# piezo-buffer-and-preamp-ritter_V0-1-thru.net
KiCad netlist of a schematic drawn in EAGLE
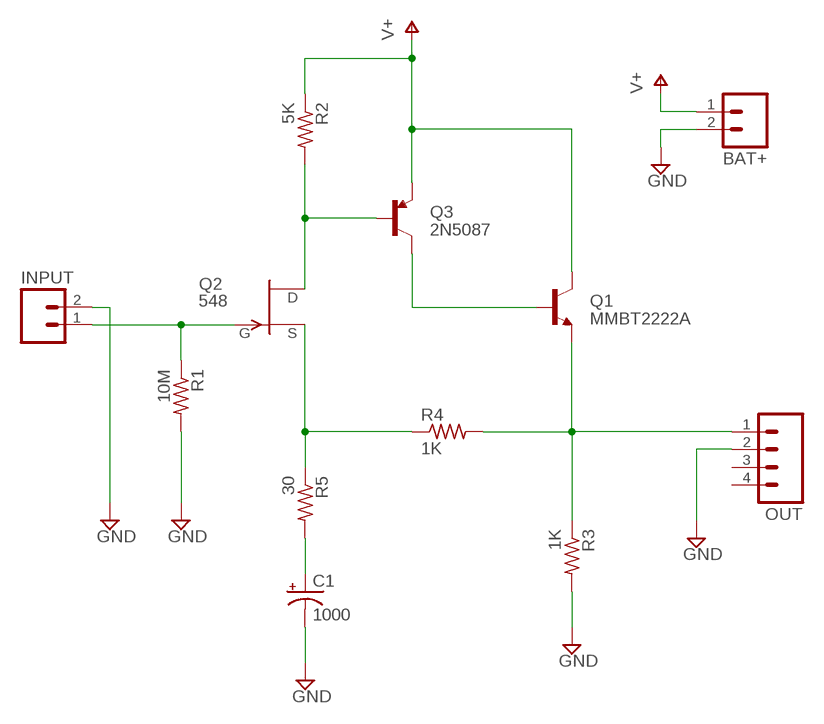
[diagram p0: schematic, sheet 1]

(export (version "E")
  (design (tool "Eeschema 10.0.6"))
  (components
    (comp (ref "BAT+")
      (value "M02LOCK")
      (footprint "eagle-import:1X02_LOCK")
      (libsource (lib "eagle-import") (part "M02LOCK"))
    )
    (comp (ref "C1")
      (value "1000")
      (footprint "eagle-import:CPOL-RADIAL-10UF-25V")
      (libsource (lib "eagle-import") (part "CAP_POLPTH2"))
    )
    (comp (ref "INPUT")
      (value "M02LOCK")
      (footprint "eagle-import:1X02_LOCK")
      (libsource (lib "eagle-import") (part "M02LOCK"))
    )
    (comp (ref "OUT")
      (value "M04PTH")
      (footprint "eagle-import:1X04")
      (libsource (lib "eagle-import") (part "M04PTH"))
    )
    (comp (ref "Q1")
      (value "MMBT2222A")
      (footprint "eagle-import:TO-92")
      (libsource (lib "eagle-import") (part "TRANSISTOR_NPNTO92"))
    )
    (comp (ref "Q2")
      (value "548")
      (footprint "eagle-import:TO-92")
      (libsource (lib "eagle-import") (part "?548"))
    )
    (comp (ref "Q3")
      (value "2N5087")
      (footprint "eagle-import:TO-92")
      (libsource (lib "eagle-import") (part "TRANSISTOR_PNPTO92"))
    )
    (comp (ref "R1")
      (value "10M")
      (footprint "eagle-import:VMTA55")
      (libsource (lib "eagle-import") (part "R-US_VMTA55"))
    )
    (comp (ref "R2")
      (value "5K")
      (footprint "eagle-import:VMTA55")
      (libsource (lib "eagle-import") (part "R-US_VMTA55"))
    )
    (comp (ref "R3")
      (value "1K")
      (footprint "eagle-import:VMTA55")
      (libsource (lib "eagle-import") (part "R-US_VMTA55"))
    )
    (comp (ref "R4")
      (value "1K")
      (footprint "eagle-import:VMTA55")
      (libsource (lib "eagle-import") (part "R-US_VMTA55"))
    )
    (comp (ref "R5")
      (value "30")
      (footprint "eagle-import:VMTA55")
      (libsource (lib "eagle-import") (part "R-US_VMTA55"))
    )
  )
  (nets
    (net (code "1") (name "GND") (class "Default")
      (node (ref "BAT+") (pin "2") (pinfunction "2_2") (pintype "passive"))
      (node (ref "C1") (pin "2") (pinfunction "-_2") (pintype "passive"))
      (node (ref "INPUT") (pin "2") (pinfunction "2_2") (pintype "passive"))
      (node (ref "OUT") (pin "2") (pinfunction "2_2") (pintype "passive"))
      (node (ref "R1") (pin "2") (pinfunction "2_2") (pintype "passive"))
      (node (ref "R3") (pin "2") (pinfunction "2_2") (pintype "passive"))
    )
    (net (code "2") (name "Net-(C1-+)") (class "Default")
      (node (ref "C1") (pin "1") (pinfunction "+_1") (pintype "passive"))
      (node (ref "R5") (pin "2") (pinfunction "2_2") (pintype "passive"))
    )
    (net (code "3") (name "Net-(Q1-B)") (class "Default")
      (node (ref "Q1") (pin "2") (pinfunction "B_2") (pintype "passive"))
      (node (ref "Q3") (pin "3") (pinfunction "C_3") (pintype "passive"))
    )
    (net (code "4") (name "Net-(Q1-E)") (class "Default")
      (node (ref "OUT") (pin "1") (pinfunction "1_1") (pintype "passive"))
      (node (ref "Q1") (pin "1") (pinfunction "E_1") (pintype "passive"))
      (node (ref "R3") (pin "1") (pinfunction "1_1") (pintype "passive"))
      (node (ref "R4") (pin "2") (pinfunction "2_2") (pintype "passive"))
    )
    (net (code "5") (name "Net-(Q2-D)") (class "Default")
      (node (ref "Q2") (pin "3") (pinfunction "D_3") (pintype "passive"))
      (node (ref "Q3") (pin "2") (pinfunction "B_2") (pintype "passive"))
      (node (ref "R2") (pin "2") (pinfunction "2_2") (pintype "passive"))
    )
    (net (code "6") (name "Net-(Q2-G)") (class "Default")
      (node (ref "INPUT") (pin "1") (pinfunction "1_1") (pintype "passive"))
      (node (ref "Q2") (pin "1") (pinfunction "G_1") (pintype "passive"))
      (node (ref "R1") (pin "1") (pinfunction "1_1") (pintype "passive"))
    )
    (net (code "7") (name "Net-(Q2-S)") (class "Default")
      (node (ref "Q2") (pin "2") (pinfunction "S_2") (pintype "passive"))
      (node (ref "R4") (pin "1") (pinfunction "1_1") (pintype "passive"))
      (node (ref "R5") (pin "1") (pinfunction "1_1") (pintype "passive"))
    )
    (net (code "8") (name "V+") (class "Default")
      (node (ref "BAT+") (pin "1") (pinfunction "1_1") (pintype "passive"))
      (node (ref "Q1") (pin "3") (pinfunction "C_3") (pintype "passive"))
      (node (ref "Q3") (pin "1") (pinfunction "E_1") (pintype "passive"))
      (node (ref "R2") (pin "1") (pinfunction "1_1") (pintype "passive"))
    )
    (net (code "9") (name "unconnected-(OUT-Pad3)") (class "Default")
      (node (ref "OUT") (pin "3") (pinfunction "3_3") (pintype "passive"))
    )
    (net (code "10") (name "unconnected-(OUT-Pad4)") (class "Default")
      (node (ref "OUT") (pin "4") (pinfunction "4_4") (pintype "passive"))
    )
  )
)
